# AMC_Connector.net
KiCad netlist of a schematic drawn in Altium Designer
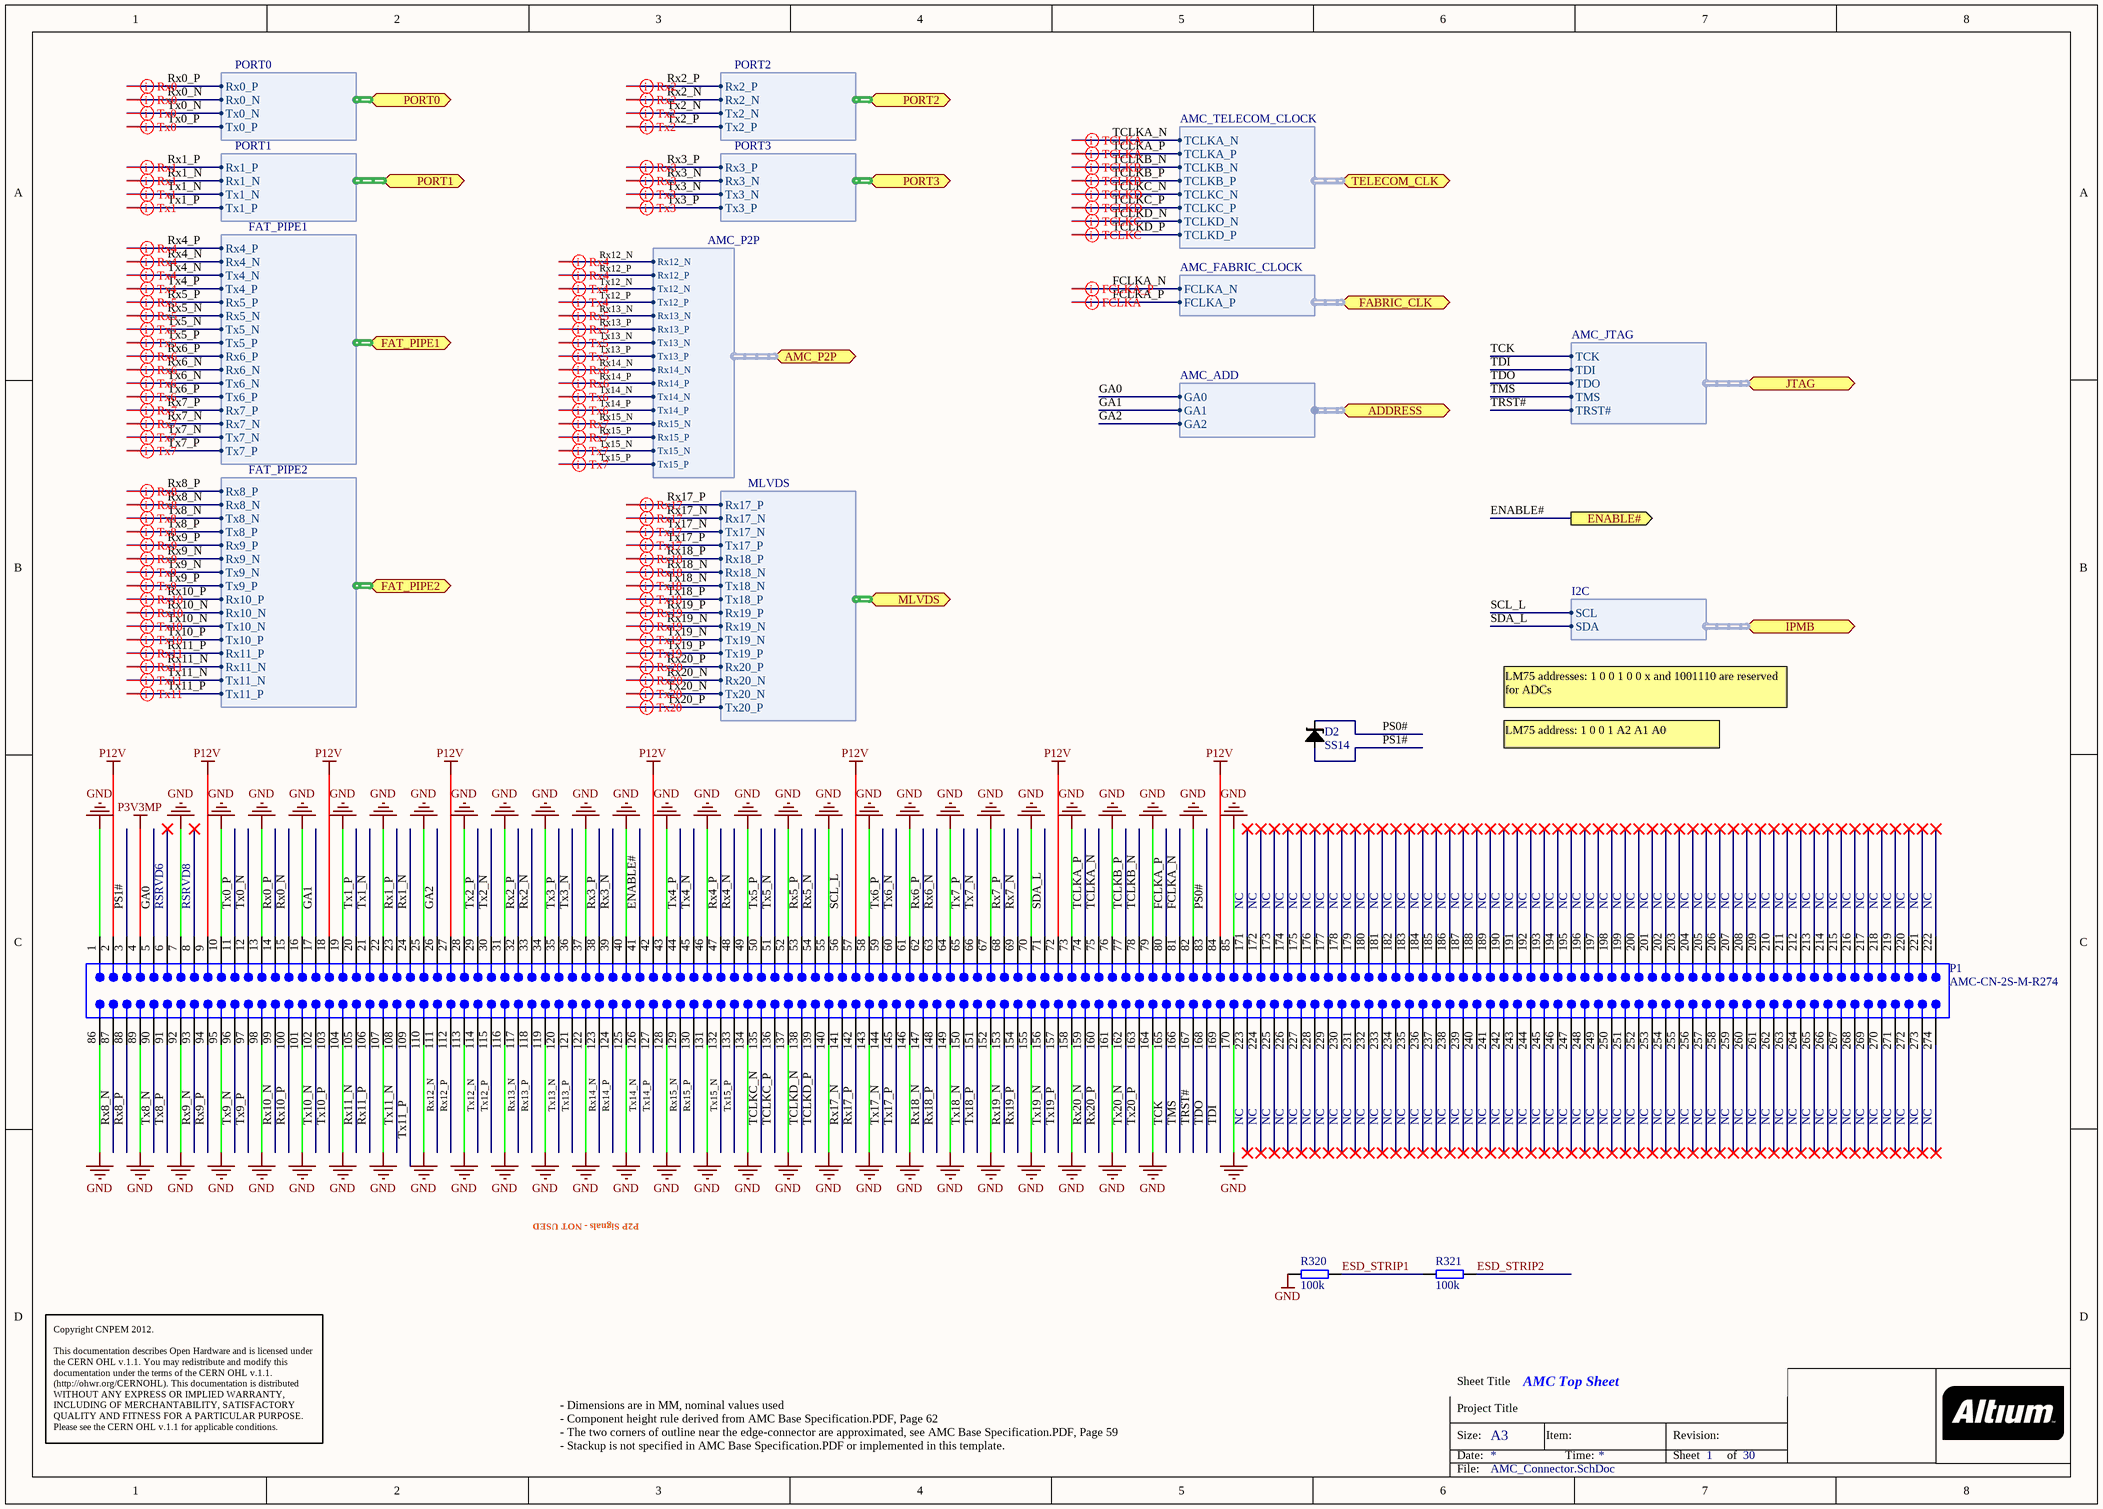
[diagram p0: AMC_Connector.SchDoc]

(export (version "E")
  (design (tool "Eeschema 10.0.6"))
  (components
    (comp (ref "D2")
      (value "SS14")
      (footprint "DO-214AC/SMA")
      (description "1A 80V shottky diode (Maritex)")
      (libsource (lib "LIBRARY_SCH") (part "D_SS14"))
    )
    (comp (ref "P1")
      (value "AMC-CN-2S-M-R274")
      (footprint "AMC-GF-2D-750-O274")
      (description "Golden finger, AMC, Dual, Opposite, Pitch 0.75mm, 170-Position")
      (fields (field (name "PUBLISHER") "Altium"))
      (libsource (lib "Altium Shanghai") (part "CMP-0001-00058-2"))
    )
    (comp (ref "R320")
      (value "100k")
      (footprint "1206R")
      (description "SMD Resistor")
      (libsource (lib "LIBRARY_SCH") (part "RES_1206"))
    )
    (comp (ref "R321")
      (value "100k")
      (footprint "1206R")
      (description "SMD Resistor")
      (libsource (lib "LIBRARY_SCH") (part "RES_1206"))
    )
  )
  (nets
    (net (code "14") (name "/ENABLE#") (class "Default")
      (node (ref "P1") (pin "41") (pinfunction "41_41") (pintype "passive"))
    )
    (net (code "15") (name "/ESD_STRIP1") (class "Default")
      (node (ref "R320") (pin "2") (pinfunction "2_2") (pintype "passive"))
      (node (ref "R321") (pin "1") (pinfunction "1_1") (pintype "passive"))
    )
    (net (code "16") (name "/ESD_STRIP2") (class "Default")
      (node (ref "R321") (pin "2") (pinfunction "2_2") (pintype "passive"))
    )
    (net (code "17") (name "/FCLKA_N") (class "Default")
      (node (ref "P1") (pin "81") (pinfunction "81_81") (pintype "passive"))
    )
    (net (code "18") (name "/FCLKA_P") (class "Default")
      (node (ref "P1") (pin "80") (pinfunction "80_80") (pintype "passive"))
    )
    (net (code "19") (name "/GA0") (class "Default")
      (node (ref "P1") (pin "5") (pinfunction "5_5") (pintype "passive"))
    )
    (net (code "20") (name "/GA1") (class "Default")
      (node (ref "P1") (pin "17") (pinfunction "17_17") (pintype "passive"))
    )
    (net (code "21") (name "/GA2") (class "Default")
      (node (ref "P1") (pin "26") (pinfunction "26_26") (pintype "passive"))
    )
    (net (code "22") (name "/PS0#") (class "Default")
      (node (ref "D2") (pin "K") (pinfunction "K_K") (pintype "passive"))
      (node (ref "P1") (pin "83") (pinfunction "83_83") (pintype "passive"))
    )
    (net (code "23") (name "/PS1#") (class "Default")
      (node (ref "D2") (pin "A") (pinfunction "A_A") (pintype "passive"))
      (node (ref "P1") (pin "3") (pinfunction "3_3") (pintype "passive"))
    )
    (net (code "24") (name "/Rx0_N") (class "Default")
      (node (ref "P1") (pin "15") (pinfunction "15_15") (pintype "passive"))
    )
    (net (code "25") (name "/Rx0_P") (class "Default")
      (node (ref "P1") (pin "14") (pinfunction "14_14") (pintype "passive"))
    )
    (net (code "26") (name "/Rx1_N") (class "Default")
      (node (ref "P1") (pin "24") (pinfunction "24_24") (pintype "passive"))
    )
    (net (code "27") (name "/Rx1_P") (class "Default")
      (node (ref "P1") (pin "23") (pinfunction "23_23") (pintype "passive"))
    )
    (net (code "28") (name "/Rx2_N") (class "Default")
      (node (ref "P1") (pin "33") (pinfunction "33_33") (pintype "passive"))
    )
    (net (code "29") (name "/Rx2_P") (class "Default")
      (node (ref "P1") (pin "32") (pinfunction "32_32") (pintype "passive"))
    )
    (net (code "30") (name "/Rx3_N") (class "Default")
      (node (ref "P1") (pin "39") (pinfunction "39_39") (pintype "passive"))
    )
    (net (code "31") (name "/Rx3_P") (class "Default")
      (node (ref "P1") (pin "38") (pinfunction "38_38") (pintype "passive"))
    )
    (net (code "32") (name "/Rx4_N") (class "Default")
      (node (ref "P1") (pin "48") (pinfunction "48_48") (pintype "passive"))
    )
    (net (code "33") (name "/Rx4_P") (class "Default")
      (node (ref "P1") (pin "47") (pinfunction "47_47") (pintype "passive"))
    )
    (net (code "34") (name "/Rx5_N") (class "Default")
      (node (ref "P1") (pin "54") (pinfunction "54_54") (pintype "passive"))
    )
    (net (code "35") (name "/Rx5_P") (class "Default")
      (node (ref "P1") (pin "53") (pinfunction "53_53") (pintype "passive"))
    )
    (net (code "36") (name "/Rx6_N") (class "Default")
      (node (ref "P1") (pin "63") (pinfunction "63_63") (pintype "passive"))
    )
    (net (code "37") (name "/Rx6_P") (class "Default")
      (node (ref "P1") (pin "62") (pinfunction "62_62") (pintype "passive"))
    )
    (net (code "38") (name "/Rx7_N") (class "Default")
      (node (ref "P1") (pin "69") (pinfunction "69_69") (pintype "passive"))
    )
    (net (code "39") (name "/Rx7_P") (class "Default")
      (node (ref "P1") (pin "68") (pinfunction "68_68") (pintype "passive"))
    )
    (net (code "40") (name "/Rx8_N") (class "Default")
      (node (ref "P1") (pin "87") (pinfunction "87_87") (pintype "passive"))
    )
    (net (code "41") (name "/Rx8_P") (class "Default")
      (node (ref "P1") (pin "88") (pinfunction "88_88") (pintype "passive"))
    )
    (net (code "42") (name "/Rx9_N") (class "Default")
      (node (ref "P1") (pin "93") (pinfunction "93_93") (pintype "passive"))
    )
    (net (code "43") (name "/Rx9_P") (class "Default")
      (node (ref "P1") (pin "94") (pinfunction "94_94") (pintype "passive"))
    )
    (net (code "44") (name "/Rx10_N") (class "Default")
      (node (ref "P1") (pin "99") (pinfunction "99_99") (pintype "passive"))
    )
    (net (code "45") (name "/Rx10_P") (class "Default")
      (node (ref "P1") (pin "100") (pinfunction "100_100") (pintype "passive"))
    )
    (net (code "46") (name "/Rx11_N") (class "Default")
      (node (ref "P1") (pin "105") (pinfunction "105_105") (pintype "passive"))
    )
    (net (code "47") (name "/Rx11_P") (class "Default")
      (node (ref "P1") (pin "106") (pinfunction "106_106") (pintype "passive"))
    )
    (net (code "48") (name "/Rx12_N") (class "Default")
      (node (ref "P1") (pin "111") (pinfunction "111_111") (pintype "passive"))
    )
    (net (code "49") (name "/Rx12_P") (class "Default")
      (node (ref "P1") (pin "112") (pinfunction "112_112") (pintype "passive"))
    )
    (net (code "50") (name "/Rx13_N") (class "Default")
      (node (ref "P1") (pin "117") (pinfunction "117_117") (pintype "passive"))
    )
    (net (code "51") (name "/Rx13_P") (class "Default")
      (node (ref "P1") (pin "118") (pinfunction "118_118") (pintype "passive"))
    )
    (net (code "52") (name "/Rx14_N") (class "Default")
      (node (ref "P1") (pin "123") (pinfunction "123_123") (pintype "passive"))
    )
    (net (code "53") (name "/Rx14_P") (class "Default")
      (node (ref "P1") (pin "124") (pinfunction "124_124") (pintype "passive"))
    )
    (net (code "54") (name "/Rx15_N") (class "Default")
      (node (ref "P1") (pin "129") (pinfunction "129_129") (pintype "passive"))
    )
    (net (code "55") (name "/Rx15_P") (class "Default")
      (node (ref "P1") (pin "130") (pinfunction "130_130") (pintype "passive"))
    )
    (net (code "56") (name "/Rx17_N") (class "Default")
      (node (ref "P1") (pin "141") (pinfunction "141_141") (pintype "passive"))
    )
    (net (code "57") (name "/Rx17_P") (class "Default")
      (node (ref "P1") (pin "142") (pinfunction "142_142") (pintype "passive"))
    )
    (net (code "58") (name "/Rx18_N") (class "Default")
      (node (ref "P1") (pin "147") (pinfunction "147_147") (pintype "passive"))
    )
    (net (code "59") (name "/Rx18_P") (class "Default")
      (node (ref "P1") (pin "148") (pinfunction "148_148") (pintype "passive"))
    )
    (net (code "60") (name "/Rx19_N") (class "Default")
      (node (ref "P1") (pin "153") (pinfunction "153_153") (pintype "passive"))
    )
    (net (code "61") (name "/Rx19_P") (class "Default")
      (node (ref "P1") (pin "154") (pinfunction "154_154") (pintype "passive"))
    )
    (net (code "62") (name "/Rx20_N") (class "Default")
      (node (ref "P1") (pin "159") (pinfunction "159_159") (pintype "passive"))
    )
    (net (code "63") (name "/Rx20_P") (class "Default")
      (node (ref "P1") (pin "160") (pinfunction "160_160") (pintype "passive"))
    )
    (net (code "64") (name "/SCL_L") (class "Default")
      (node (ref "P1") (pin "56") (pinfunction "56_56") (pintype "passive"))
    )
    (net (code "65") (name "/SDA_L") (class "Default")
      (node (ref "P1") (pin "71") (pinfunction "71_71") (pintype "passive"))
    )
    (net (code "66") (name "/TCK") (class "Default")
      (node (ref "P1") (pin "165") (pinfunction "165_165") (pintype "passive"))
    )
    (net (code "67") (name "/TCLKA_N") (class "Default")
      (node (ref "P1") (pin "75") (pinfunction "75_75") (pintype "passive"))
    )
    (net (code "68") (name "/TCLKA_P") (class "Default")
      (node (ref "P1") (pin "74") (pinfunction "74_74") (pintype "passive"))
    )
    (net (code "69") (name "/TCLKB_N") (class "Default")
      (node (ref "P1") (pin "78") (pinfunction "78_78") (pintype "passive"))
    )
    (net (code "70") (name "/TCLKB_P") (class "Default")
      (node (ref "P1") (pin "77") (pinfunction "77_77") (pintype "passive"))
    )
    (net (code "71") (name "/TCLKC_N") (class "Default")
      (node (ref "P1") (pin "135") (pinfunction "135_135") (pintype "passive"))
    )
    (net (code "72") (name "/TCLKC_P") (class "Default")
      (node (ref "P1") (pin "136") (pinfunction "136_136") (pintype "passive"))
    )
    (net (code "73") (name "/TCLKD_N") (class "Default")
      (node (ref "P1") (pin "138") (pinfunction "138_138") (pintype "passive"))
    )
    (net (code "74") (name "/TCLKD_P") (class "Default")
      (node (ref "P1") (pin "139") (pinfunction "139_139") (pintype "passive"))
    )
    (net (code "75") (name "/TDI") (class "Default")
      (node (ref "P1") (pin "169") (pinfunction "169_169") (pintype "passive"))
    )
    (net (code "76") (name "/TDO") (class "Default")
      (node (ref "P1") (pin "168") (pinfunction "168_168") (pintype "passive"))
    )
    (net (code "77") (name "/TMS") (class "Default")
      (node (ref "P1") (pin "166") (pinfunction "166_166") (pintype "passive"))
    )
    (net (code "78") (name "/TRST#") (class "Default")
      (node (ref "P1") (pin "167") (pinfunction "167_167") (pintype "passive"))
    )
    (net (code "79") (name "/Tx0_N") (class "Default")
      (node (ref "P1") (pin "12") (pinfunction "12_12") (pintype "passive"))
    )
    (net (code "80") (name "/Tx0_P") (class "Default")
      (node (ref "P1") (pin "11") (pinfunction "11_11") (pintype "passive"))
    )
    (net (code "81") (name "/Tx1_N") (class "Default")
      (node (ref "P1") (pin "21") (pinfunction "21_21") (pintype "passive"))
    )
    (net (code "82") (name "/Tx1_P") (class "Default")
      (node (ref "P1") (pin "20") (pinfunction "20_20") (pintype "passive"))
    )
    (net (code "83") (name "/Tx2_N") (class "Default")
      (node (ref "P1") (pin "30") (pinfunction "30_30") (pintype "passive"))
    )
    (net (code "84") (name "/Tx2_P") (class "Default")
      (node (ref "P1") (pin "29") (pinfunction "29_29") (pintype "passive"))
    )
    (net (code "85") (name "/Tx3_N") (class "Default")
      (node (ref "P1") (pin "36") (pinfunction "36_36") (pintype "passive"))
    )
    (net (code "86") (name "/Tx3_P") (class "Default")
      (node (ref "P1") (pin "35") (pinfunction "35_35") (pintype "passive"))
    )
    (net (code "87") (name "/Tx4_N") (class "Default")
      (node (ref "P1") (pin "45") (pinfunction "45_45") (pintype "passive"))
    )
    (net (code "88") (name "/Tx4_P") (class "Default")
      (node (ref "P1") (pin "44") (pinfunction "44_44") (pintype "passive"))
    )
    (net (code "89") (name "/Tx5_N") (class "Default")
      (node (ref "P1") (pin "51") (pinfunction "51_51") (pintype "passive"))
    )
    (net (code "90") (name "/Tx5_P") (class "Default")
      (node (ref "P1") (pin "50") (pinfunction "50_50") (pintype "passive"))
    )
    (net (code "91") (name "/Tx6_N") (class "Default")
      (node (ref "P1") (pin "60") (pinfunction "60_60") (pintype "passive"))
    )
    (net (code "92") (name "/Tx6_P") (class "Default")
      (node (ref "P1") (pin "59") (pinfunction "59_59") (pintype "passive"))
    )
    (net (code "93") (name "/Tx7_N") (class "Default")
      (node (ref "P1") (pin "66") (pinfunction "66_66") (pintype "passive"))
    )
    (net (code "94") (name "/Tx7_P") (class "Default")
      (node (ref "P1") (pin "65") (pinfunction "65_65") (pintype "passive"))
    )
    (net (code "95") (name "/Tx8_N") (class "Default")
      (node (ref "P1") (pin "90") (pinfunction "90_90") (pintype "passive"))
    )
    (net (code "96") (name "/Tx8_P") (class "Default")
      (node (ref "P1") (pin "91") (pinfunction "91_91") (pintype "passive"))
    )
    (net (code "97") (name "/Tx9_N") (class "Default")
      (node (ref "P1") (pin "96") (pinfunction "96_96") (pintype "passive"))
    )
    (net (code "98") (name "/Tx9_P") (class "Default")
      (node (ref "P1") (pin "97") (pinfunction "97_97") (pintype "passive"))
    )
    (net (code "99") (name "/Tx10_N") (class "Default")
      (node (ref "P1") (pin "102") (pinfunction "102_102") (pintype "passive"))
    )
    (net (code "100") (name "/Tx10_P") (class "Default")
      (node (ref "P1") (pin "103") (pinfunction "103_103") (pintype "passive"))
    )
    (net (code "101") (name "/Tx11_N") (class "Default")
      (node (ref "P1") (pin "108") (pinfunction "108_108") (pintype "passive"))
    )
    (net (code "102") (name "/Tx11_P") (class "Default")
      (node (ref "P1") (pin "109") (pinfunction "109_109") (pintype "passive"))
    )
    (net (code "103") (name "/Tx12_N") (class "Default")
      (node (ref "P1") (pin "114") (pinfunction "114_114") (pintype "passive"))
    )
    (net (code "104") (name "/Tx12_P") (class "Default")
      (node (ref "P1") (pin "115") (pinfunction "115_115") (pintype "passive"))
    )
    (net (code "105") (name "/Tx13_N") (class "Default")
      (node (ref "P1") (pin "120") (pinfunction "120_120") (pintype "passive"))
    )
    (net (code "106") (name "/Tx13_P") (class "Default")
      (node (ref "P1") (pin "121") (pinfunction "121_121") (pintype "passive"))
    )
    (net (code "107") (name "/Tx14_N") (class "Default")
      (node (ref "P1") (pin "126") (pinfunction "126_126") (pintype "passive"))
    )
    (net (code "108") (name "/Tx14_P") (class "Default")
      (node (ref "P1") (pin "127") (pinfunction "127_127") (pintype "passive"))
    )
    (net (code "109") (name "/Tx15_N") (class "Default")
      (node (ref "P1") (pin "132") (pinfunction "132_132") (pintype "passive"))
    )
    (net (code "110") (name "/Tx15_P") (class "Default")
      (node (ref "P1") (pin "133") (pinfunction "133_133") (pintype "passive"))
    )
    (net (code "111") (name "/Tx17_N") (class "Default")
      (node (ref "P1") (pin "144") (pinfunction "144_144") (pintype "passive"))
    )
    (net (code "112") (name "/Tx17_P") (class "Default")
      (node (ref "P1") (pin "145") (pinfunction "145_145") (pintype "passive"))
    )
    (net (code "113") (name "/Tx18_N") (class "Default")
      (node (ref "P1") (pin "150") (pinfunction "150_150") (pintype "passive"))
    )
    (net (code "114") (name "/Tx18_P") (class "Default")
      (node (ref "P1") (pin "151") (pinfunction "151_151") (pintype "passive"))
    )
    (net (code "115") (name "/Tx19_N") (class "Default")
      (node (ref "P1") (pin "156") (pinfunction "156_156") (pintype "passive"))
    )
    (net (code "116") (name "/Tx19_P") (class "Default")
      (node (ref "P1") (pin "157") (pinfunction "157_157") (pintype "passive"))
    )
    (net (code "117") (name "/Tx20_N") (class "Default")
      (node (ref "P1") (pin "162") (pinfunction "162_162") (pintype "passive"))
    )
    (net (code "118") (name "/Tx20_P") (class "Default")
      (node (ref "P1") (pin "163") (pinfunction "163_163") (pintype "passive"))
    )
    (net (code "132") (name "GND") (class "Default")
      (node (ref "P1") (pin "1") (pinfunction "1_1") (pintype "passive"))
      (node (ref "P1") (pin "10") (pinfunction "10_10") (pintype "passive"))
      (node (ref "P1") (pin "101") (pinfunction "101_101") (pintype "passive"))
      (node (ref "P1") (pin "104") (pinfunction "104_104") (pintype "passive"))
      (node (ref "P1") (pin "107") (pinfunction "107_107") (pintype "passive"))
      (node (ref "P1") (pin "110") (pinfunction "110_110") (pintype "passive"))
      (node (ref "P1") (pin "113") (pinfunction "113_113") (pintype "passive"))
      (node (ref "P1") (pin "116") (pinfunction "116_116") (pintype "passive"))
      (node (ref "P1") (pin "119") (pinfunction "119_119") (pintype "passive"))
      (node (ref "P1") (pin "122") (pinfunction "122_122") (pintype "passive"))
      (node (ref "P1") (pin "125") (pinfunction "125_125") (pintype "passive"))
      (node (ref "P1") (pin "128") (pinfunction "128_128") (pintype "passive"))
      (node (ref "P1") (pin "13") (pinfunction "13_13") (pintype "passive"))
      (node (ref "P1") (pin "131") (pinfunction "131_131") (pintype "passive"))
      (node (ref "P1") (pin "134") (pinfunction "134_134") (pintype "passive"))
      (node (ref "P1") (pin "137") (pinfunction "137_137") (pintype "passive"))
      (node (ref "P1") (pin "140") (pinfunction "140_140") (pintype "passive"))
      (node (ref "P1") (pin "143") (pinfunction "143_143") (pintype "passive"))
      (node (ref "P1") (pin "146") (pinfunction "146_146") (pintype "passive"))
      (node (ref "P1") (pin "149") (pinfunction "149_149") (pintype "passive"))
      (node (ref "P1") (pin "152") (pinfunction "152_152") (pintype "passive"))
      (node (ref "P1") (pin "155") (pinfunction "155_155") (pintype "passive"))
      (node (ref "P1") (pin "158") (pinfunction "158_158") (pintype "passive"))
      (node (ref "P1") (pin "16") (pinfunction "16_16") (pintype "passive"))
      (node (ref "P1") (pin "161") (pinfunction "161_161") (pintype "passive"))
      (node (ref "P1") (pin "164") (pinfunction "164_164") (pintype "passive"))
      (node (ref "P1") (pin "170") (pinfunction "170_170") (pintype "passive"))
      (node (ref "P1") (pin "19") (pinfunction "19_19") (pintype "passive"))
      (node (ref "P1") (pin "22") (pinfunction "22_22") (pintype "passive"))
      (node (ref "P1") (pin "25") (pinfunction "25_25") (pintype "passive"))
      (node (ref "P1") (pin "28") (pinfunction "28_28") (pintype "passive"))
      (node (ref "P1") (pin "31") (pinfunction "31_31") (pintype "passive"))
      (node (ref "P1") (pin "34") (pinfunction "34_34") (pintype "passive"))
      (node (ref "P1") (pin "37") (pinfunction "37_37") (pintype "passive"))
      (node (ref "P1") (pin "40") (pinfunction "40_40") (pintype "passive"))
      (node (ref "P1") (pin "43") (pinfunction "43_43") (pintype "passive"))
      (node (ref "P1") (pin "46") (pinfunction "46_46") (pintype "passive"))
      (node (ref "P1") (pin "49") (pinfunction "49_49") (pintype "passive"))
      (node (ref "P1") (pin "52") (pinfunction "52_52") (pintype "passive"))
      (node (ref "P1") (pin "55") (pinfunction "55_55") (pintype "passive"))
      (node (ref "P1") (pin "58") (pinfunction "58_58") (pintype "passive"))
      (node (ref "P1") (pin "61") (pinfunction "61_61") (pintype "passive"))
      (node (ref "P1") (pin "64") (pinfunction "64_64") (pintype "passive"))
      (node (ref "P1") (pin "67") (pinfunction "67_67") (pintype "passive"))
      (node (ref "P1") (pin "7") (pinfunction "7_7") (pintype "passive"))
      (node (ref "P1") (pin "70") (pinfunction "70_70") (pintype "passive"))
      (node (ref "P1") (pin "73") (pinfunction "73_73") (pintype "passive"))
      (node (ref "P1") (pin "76") (pinfunction "76_76") (pintype "passive"))
      (node (ref "P1") (pin "79") (pinfunction "79_79") (pintype "passive"))
      (node (ref "P1") (pin "82") (pinfunction "82_82") (pintype "passive"))
      (node (ref "P1") (pin "85") (pinfunction "85_85") (pintype "passive"))
      (node (ref "P1") (pin "86") (pinfunction "86_86") (pintype "passive"))
      (node (ref "P1") (pin "89") (pinfunction "89_89") (pintype "passive"))
      (node (ref "P1") (pin "92") (pinfunction "92_92") (pintype "passive"))
      (node (ref "P1") (pin "95") (pinfunction "95_95") (pintype "passive"))
      (node (ref "P1") (pin "98") (pinfunction "98_98") (pintype "passive"))
      (node (ref "R320") (pin "1") (pinfunction "1_1") (pintype "passive"))
    )
    (net (code "133") (name "P3V3MP") (class "Default")
      (node (ref "P1") (pin "4") (pinfunction "4_4") (pintype "passive"))
    )
    (net (code "134") (name "P12V") (class "Default")
      (node (ref "P1") (pin "18") (pinfunction "18_18") (pintype "passive"))
      (node (ref "P1") (pin "2") (pinfunction "2_2") (pintype "passive"))
      (node (ref "P1") (pin "27") (pinfunction "27_27") (pintype "passive"))
      (node (ref "P1") (pin "42") (pinfunction "42_42") (pintype "passive"))
      (node (ref "P1") (pin "57") (pinfunction "57_57") (pintype "passive"))
      (node (ref "P1") (pin "72") (pinfunction "72_72") (pintype "passive"))
      (node (ref "P1") (pin "84") (pinfunction "84_84") (pintype "passive"))
      (node (ref "P1") (pin "9") (pinfunction "9_9") (pintype "passive"))
    )
    (net (code "135") (name "unconnected-(P1-Pad6)") (class "Default")
      (node (ref "P1") (pin "6") (pinfunction "6_6") (pintype "passive+no_connect"))
    )
    (net (code "136") (name "unconnected-(P1-Pad8)") (class "Default")
      (node (ref "P1") (pin "8") (pinfunction "8_8") (pintype "passive+no_connect"))
    )
    (net (code "137") (name "unconnected-(P1-Pad171)") (class "Default")
      (node (ref "P1") (pin "171") (pinfunction "171_171") (pintype "passive+no_connect"))
    )
    (net (code "138") (name "unconnected-(P1-Pad172)") (class "Default")
      (node (ref "P1") (pin "172") (pinfunction "172_172") (pintype "passive+no_connect"))
    )
    (net (code "139") (name "unconnected-(P1-Pad173)") (class "Default")
      (node (ref "P1") (pin "173") (pinfunction "173_173") (pintype "passive+no_connect"))
    )
    (net (code "140") (name "unconnected-(P1-Pad174)") (class "Default")
      (node (ref "P1") (pin "174") (pinfunction "174_174") (pintype "passive+no_connect"))
    )
    (net (code "141") (name "unconnected-(P1-Pad175)") (class "Default")
      (node (ref "P1") (pin "175") (pinfunction "175_175") (pintype "passive+no_connect"))
    )
    (net (code "142") (name "unconnected-(P1-Pad176)") (class "Default")
      (node (ref "P1") (pin "176") (pinfunction "176_176") (pintype "passive+no_connect"))
    )
    (net (code "143") (name "unconnected-(P1-Pad177)") (class "Default")
      (node (ref "P1") (pin "177") (pinfunction "177_177") (pintype "passive+no_connect"))
    )
    (net (code "144") (name "unconnected-(P1-Pad178)") (class "Default")
      (node (ref "P1") (pin "178") (pinfunction "178_178") (pintype "passive+no_connect"))
    )
    (net (code "145") (name "unconnected-(P1-Pad179)") (class "Default")
      (node (ref "P1") (pin "179") (pinfunction "179_179") (pintype "passive+no_connect"))
    )
    (net (code "146") (name "unconnected-(P1-Pad180)") (class "Default")
      (node (ref "P1") (pin "180") (pinfunction "180_180") (pintype "passive+no_connect"))
    )
    (net (code "147") (name "unconnected-(P1-Pad181)") (class "Default")
      (node (ref "P1") (pin "181") (pinfunction "181_181") (pintype "passive+no_connect"))
    )
    (net (code "148") (name "unconnected-(P1-Pad182)") (class "Default")
      (node (ref "P1") (pin "182") (pinfunction "182_182") (pintype "passive+no_connect"))
    )
    (net (code "149") (name "unconnected-(P1-Pad183)") (class "Default")
      (node (ref "P1") (pin "183") (pinfunction "183_183") (pintype "passive+no_connect"))
    )
    (net (code "150") (name "unconnected-(P1-Pad184)") (class "Default")
      (node (ref "P1") (pin "184") (pinfunction "184_184") (pintype "passive+no_connect"))
    )
    (net (code "151") (name "unconnected-(P1-Pad185)") (class "Default")
      (node (ref "P1") (pin "185") (pinfunction "185_185") (pintype "passive+no_connect"))
    )
    (net (code "152") (name "unconnected-(P1-Pad186)") (class "Default")
      (node (ref "P1") (pin "186") (pinfunction "186_186") (pintype "passive+no_connect"))
    )
    (net (code "153") (name "unconnected-(P1-Pad187)") (class "Default")
      (node (ref "P1") (pin "187") (pinfunction "187_187") (pintype "passive+no_connect"))
    )
    (net (code "154") (name "unconnected-(P1-Pad188)") (class "Default")
      (node (ref "P1") (pin "188") (pinfunction "188_188") (pintype "passive+no_connect"))
    )
    (net (code "155") (name "unconnected-(P1-Pad189)") (class "Default")
      (node (ref "P1") (pin "189") (pinfunction "189_189") (pintype "passive+no_connect"))
    )
    (net (code "156") (name "unconnected-(P1-Pad190)") (class "Default")
      (node (ref "P1") (pin "190") (pinfunction "190_190") (pintype "passive+no_connect"))
    )
    (net (code "157") (name "unconnected-(P1-Pad191)") (class "Default")
      (node (ref "P1") (pin "191") (pinfunction "191_191") (pintype "passive+no_connect"))
    )
    (net (code "158") (name "unconnected-(P1-Pad192)") (class "Default")
      (node (ref "P1") (pin "192") (pinfunction "192_192") (pintype "passive+no_connect"))
    )
    (net (code "159") (name "unconnected-(P1-Pad193)") (class "Default")
      (node (ref "P1") (pin "193") (pinfunction "193_193") (pintype "passive+no_connect"))
    )
    (net (code "160") (name "unconnected-(P1-Pad194)") (class "Default")
      (node (ref "P1") (pin "194") (pinfunction "194_194") (pintype "passive+no_connect"))
    )
    (net (code "161") (name "unconnected-(P1-Pad195)") (class "Default")
      (node (ref "P1") (pin "195") (pinfunction "195_195") (pintype "passive+no_connect"))
    )
    (net (code "162") (name "unconnected-(P1-Pad196)") (class "Default")
      (node (ref "P1") (pin "196") (pinfunction "196_196") (pintype "passive+no_connect"))
    )
    (net (code "163") (name "unconnected-(P1-Pad197)") (class "Default")
      (node (ref "P1") (pin "197") (pinfunction "197_197") (pintype "passive+no_connect"))
    )
    (net (code "164") (name "unconnected-(P1-Pad198)") (class "Default")
      (node (ref "P1") (pin "198") (pinfunction "198_198") (pintype "passive+no_connect"))
    )
    (net (code "165") (name "unconnected-(P1-Pad199)") (class "Default")
      (node (ref "P1") (pin "199") (pinfunction "199_199") (pintype "passive+no_connect"))
    )
    (net (code "166") (name "unconnected-(P1-Pad200)") (class "Default")
      (node (ref "P1") (pin "200") (pinfunction "200_200") (pintype "passive+no_connect"))
    )
    (net (code "167") (name "unconnected-(P1-Pad201)") (class "Default")
      (node (ref "P1") (pin "201") (pinfunction "201_201") (pintype "passive+no_connect"))
    )
    (net (code "168") (name "unconnected-(P1-Pad202)") (class "Default")
      (node (ref "P1") (pin "202") (pinfunction "202_202") (pintype "passive+no_connect"))
    )
    (net (code "169") (name "unconnected-(P1-Pad203)") (class "Default")
      (node (ref "P1") (pin "203") (pinfunction "203_203") (pintype "passive+no_connect"))
    )
    (net (code "170") (name "unconnected-(P1-Pad204)") (class "Default")
      (node (ref "P1") (pin "204") (pinfunction "204_204") (pintype "passive+no_connect"))
    )
    (net (code "171") (name "unconnected-(P1-Pad205)") (class "Default")
      (node (ref "P1") (pin "205") (pinfunction "205_205") (pintype "passive+no_connect"))
    )
    (net (code "172") (name "unconnected-(P1-Pad206)") (class "Default")
      (node (ref "P1") (pin "206") (pinfunction "206_206") (pintype "passive+no_connect"))
    )
    (net (code "173") (name "unconnected-(P1-Pad207)") (class "Default")
      (node (ref "P1") (pin "207") (pinfunction "207_207") (pintype "passive+no_connect"))
    )
    (net (code "174") (name "unconnected-(P1-Pad208)") (class "Default")
      (node (ref "P1") (pin "208") (pinfunction "208_208") (pintype "passive+no_connect"))
    )
    (net (code "175") (name "unconnected-(P1-Pad209)") (class "Default")
      (node (ref "P1") (pin "209") (pinfunction "209_209") (pintype "passive+no_connect"))
    )
    (net (code "176") (name "unconnected-(P1-Pad210)") (class "Default")
      (node (ref "P1") (pin "210") (pinfunction "210_210") (pintype "passive+no_connect"))
    )
    (net (code "177") (name "unconnected-(P1-Pad211)") (class "Default")
      (node (ref "P1") (pin "211") (pinfunction "211_211") (pintype "passive+no_connect"))
    )
    (net (code "178") (name "unconnected-(P1-Pad212)") (class "Default")
      (node (ref "P1") (pin "212") (pinfunction "212_212") (pintype "passive+no_connect"))
    )
    (net (code "179") (name "unconnected-(P1-Pad213)") (class "Default")
      (node (ref "P1") (pin "213") (pinfunction "213_213") (pintype "passive+no_connect"))
    )
    (net (code "180") (name "unconnected-(P1-Pad214)") (class "Default")
      (node (ref "P1") (pin "214") (pinfunction "214_214") (pintype "passive+no_connect"))
    )
    (net (code "181") (name "unconnected-(P1-Pad215)") (class "Default")
      (node (ref "P1") (pin "215") (pinfunction "215_215") (pintype "passive+no_connect"))
    )
    (net (code "182") (name "unconnected-(P1-Pad216)") (class "Default")
      (node (ref "P1") (pin "216") (pinfunction "216_216") (pintype "passive+no_connect"))
    )
    (net (code "183") (name "unconnected-(P1-Pad217)") (class "Default")
      (node (ref "P1") (pin "217") (pinfunction "217_217") (pintype "passive+no_connect"))
    )
    (net (code "184") (name "unconnected-(P1-Pad218)") (class "Default")
      (node (ref "P1") (pin "218") (pinfunction "218_218") (pintype "passive+no_connect"))
    )
    (net (code "185") (name "unconnected-(P1-Pad219)") (class "Default")
      (node (ref "P1") (pin "219") (pinfunction "219_219") (pintype "passive+no_connect"))
    )
    (net (code "186") (name "unconnected-(P1-Pad220)") (class "Default")
      (node (ref "P1") (pin "220") (pinfunction "220_220") (pintype "passive+no_connect"))
    )
    (net (code "187") (name "unconnected-(P1-Pad221)") (class "Default")
      (node (ref "P1") (pin "221") (pinfunction "221_221") (pintype "passive+no_connect"))
    )
    (net (code "188") (name "unconnected-(P1-Pad222)") (class "Default")
      (node (ref "P1") (pin "222") (pinfunction "222_222") (pintype "passive+no_connect"))
    )
    (net (code "189") (name "unconnected-(P1-Pad223)") (class "Default")
      (node (ref "P1") (pin "223") (pinfunction "223_223") (pintype "passive+no_connect"))
    )
    (net (code "190") (name "unconnected-(P1-Pad224)") (class "Default")
      (node (ref "P1") (pin "224") (pinfunction "224_224") (pintype "passive+no_connect"))
    )
    (net (code "191") (name "unconnected-(P1-Pad225)") (class "Default")
      (node (ref "P1") (pin "225") (pinfunction "225_225") (pintype "passive+no_connect"))
    )
    (net (code "192") (name "unconnected-(P1-Pad226)") (class "Default")
      (node (ref "P1") (pin "226") (pinfunction "226_226") (pintype "passive+no_connect"))
    )
    (net (code "193") (name "unconnected-(P1-Pad227)") (class "Default")
      (node (ref "P1") (pin "227") (pinfunction "227_227") (pintype "passive+no_connect"))
    )
    (net (code "194") (name "unconnected-(P1-Pad228)") (class "Default")
      (node (ref "P1") (pin "228") (pinfunction "228_228") (pintype "passive+no_connect"))
    )
    (net (code "195") (name "unconnected-(P1-Pad229)") (class "Default")
      (node (ref "P1") (pin "229") (pinfunction "229_229") (pintype "passive+no_connect"))
    )
    (net (code "196") (name "unconnected-(P1-Pad230)") (class "Default")
      (node (ref "P1") (pin "230") (pinfunction "230_230") (pintype "passive+no_connect"))
    )
    (net (code "197") (name "unconnected-(P1-Pad231)") (class "Default")
      (node (ref "P1") (pin "231") (pinfunction "231_231") (pintype "passive+no_connect"))
    )
    (net (code "198") (name "unconnected-(P1-Pad232)") (class "Default")
      (node (ref "P1") (pin "232") (pinfunction "232_232") (pintype "passive+no_connect"))
    )
    (net (code "199") (name "unconnected-(P1-Pad233)") (class "Default")
      (node (ref "P1") (pin "233") (pinfunction "233_233") (pintype "passive+no_connect"))
    )
    (net (code "200") (name "unconnected-(P1-Pad234)") (class "Default")
      (node (ref "P1") (pin "234") (pinfunction "234_234") (pintype "passive+no_connect"))
    )
    (net (code "201") (name "unconnected-(P1-Pad235)") (class "Default")
      (node (ref "P1") (pin "235") (pinfunction "235_235") (pintype "passive+no_connect"))
    )
    (net (code "202") (name "unconnected-(P1-Pad236)") (class "Default")
      (node (ref "P1") (pin "236") (pinfunction "236_236") (pintype "passive+no_connect"))
    )
    (net (code "203") (name "unconnected-(P1-Pad237)") (class "Default")
      (node (ref "P1") (pin "237") (pinfunction "237_237") (pintype "passive+no_connect"))
    )
    (net (code "204") (name "unconnected-(P1-Pad238)") (class "Default")
      (node (ref "P1") (pin "238") (pinfunction "238_238") (pintype "passive+no_connect"))
    )
    (net (code "205") (name "unconnected-(P1-Pad239)") (class "Default")
      (node (ref "P1") (pin "239") (pinfunction "239_239") (pintype "passive+no_connect"))
    )
    (net (code "206") (name "unconnected-(P1-Pad240)") (class "Default")
      (node (ref "P1") (pin "240") (pinfunction "240_240") (pintype "passive+no_connect"))
    )
    (net (code "207") (name "unconnected-(P1-Pad241)") (class "Default")
      (node (ref "P1") (pin "241") (pinfunction "241_241") (pintype "passive+no_connect"))
    )
    (net (code "208") (name "unconnected-(P1-Pad242)") (class "Default")
      (node (ref "P1") (pin "242") (pinfunction "242_242") (pintype "passive+no_connect"))
    )
    (net (code "209") (name "unconnected-(P1-Pad243)") (class "Default")
      (node (ref "P1") (pin "243") (pinfunction "243_243") (pintype "passive+no_connect"))
    )
    (net (code "210") (name "unconnected-(P1-Pad244)") (class "Default")
      (node (ref "P1") (pin "244") (pinfunction "244_244") (pintype "passive+no_connect"))
    )
    (net (code "211") (name "unconnected-(P1-Pad245)") (class "Default")
      (node (ref "P1") (pin "245") (pinfunction "245_245") (pintype "passive+no_connect"))
    )
    (net (code "212") (name "unconnected-(P1-Pad246)") (class "Default")
      (node (ref "P1") (pin "246") (pinfunction "246_246") (pintype "passive+no_connect"))
    )
    (net (code "213") (name "unconnected-(P1-Pad247)") (class "Default")
      (node (ref "P1") (pin "247") (pinfunction "247_247") (pintype "passive+no_connect"))
    )
    (net (code "214") (name "unconnected-(P1-Pad248)") (class "Default")
      (node (ref "P1") (pin "248") (pinfunction "248_248") (pintype "passive+no_connect"))
    )
    (net (code "215") (name "unconnected-(P1-Pad249)") (class "Default")
      (node (ref "P1") (pin "249") (pinfunction "249_249") (pintype "passive+no_connect"))
    )
    (net (code "216") (name "unconnected-(P1-Pad250)") (class "Default")
      (node (ref "P1") (pin "250") (pinfunction "250_250") (pintype "passive+no_connect"))
    )
    (net (code "217") (name "unconnected-(P1-Pad251)") (class "Default")
      (node (ref "P1") (pin "251") (pinfunction "251_251") (pintype "passive+no_connect"))
    )
    (net (code "218") (name "unconnected-(P1-Pad252)") (class "Default")
      (node (ref "P1") (pin "252") (pinfunction "252_252") (pintype "passive+no_connect"))
    )
    (net (code "219") (name "unconnected-(P1-Pad253)") (class "Default")
      (node (ref "P1") (pin "253") (pinfunction "253_253") (pintype "passive+no_connect"))
    )
    (net (code "220") (name "unconnected-(P1-Pad254)") (class "Default")
      (node (ref "P1") (pin "254") (pinfunction "254_254") (pintype "passive+no_connect"))
    )
    (net (code "221") (name "unconnected-(P1-Pad255)") (class "Default")
      (node (ref "P1") (pin "255") (pinfunction "255_255") (pintype "passive+no_connect"))
    )
    (net (code "222") (name "unconnected-(P1-Pad256)") (class "Default")
      (node (ref "P1") (pin "256") (pinfunction "256_256") (pintype "passive+no_connect"))
    )
    (net (code "223") (name "unconnected-(P1-Pad257)") (class "Default")
      (node (ref "P1") (pin "257") (pinfunction "257_257") (pintype "passive+no_connect"))
    )
    (net (code "224") (name "unconnected-(P1-Pad258)") (class "Default")
      (node (ref "P1") (pin "258") (pinfunction "258_258") (pintype "passive+no_connect"))
    )
    (net (code "225") (name "unconnected-(P1-Pad259)") (class "Default")
      (node (ref "P1") (pin "259") (pinfunction "259_259") (pintype "passive+no_connect"))
    )
    (net (code "226") (name "unconnected-(P1-Pad260)") (class "Default")
      (node (ref "P1") (pin "260") (pinfunction "260_260") (pintype "passive+no_connect"))
    )
    (net (code "227") (name "unconnected-(P1-Pad261)") (class "Default")
      (node (ref "P1") (pin "261") (pinfunction "261_261") (pintype "passive+no_connect"))
    )
    (net (code "228") (name "unconnected-(P1-Pad262)") (class "Default")
      (node (ref "P1") (pin "262") (pinfunction "262_262") (pintype "passive+no_connect"))
    )
    (net (code "229") (name "unconnected-(P1-Pad263)") (class "Default")
      (node (ref "P1") (pin "263") (pinfunction "263_263") (pintype "passive+no_connect"))
    )
    (net (code "230") (name "unconnected-(P1-Pad264)") (class "Default")
      (node (ref "P1") (pin "264") (pinfunction "264_264") (pintype "passive+no_connect"))
    )
    (net (code "231") (name "unconnected-(P1-Pad265)") (class "Default")
      (node (ref "P1") (pin "265") (pinfunction "265_265") (pintype "passive+no_connect"))
    )
    (net (code "232") (name "unconnected-(P1-Pad266)") (class "Default")
      (node (ref "P1") (pin "266") (pinfunction "266_266") (pintype "passive+no_connect"))
    )
    (net (code "233") (name "unconnected-(P1-Pad267)") (class "Default")
      (node (ref "P1") (pin "267") (pinfunction "267_267") (pintype "passive+no_connect"))
    )
    (net (code "234") (name "unconnected-(P1-Pad268)") (class "Default")
      (node (ref "P1") (pin "268") (pinfunction "268_268") (pintype "passive+no_connect"))
    )
    (net (code "235") (name "unconnected-(P1-Pad269)") (class "Default")
      (node (ref "P1") (pin "269") (pinfunction "269_269") (pintype "passive+no_connect"))
    )
    (net (code "236") (name "unconnected-(P1-Pad270)") (class "Default")
      (node (ref "P1") (pin "270") (pinfunction "270_270") (pintype "passive+no_connect"))
    )
    (net (code "237") (name "unconnected-(P1-Pad271)") (class "Default")
      (node (ref "P1") (pin "271") (pinfunction "271_271") (pintype "passive+no_connect"))
    )
    (net (code "238") (name "unconnected-(P1-Pad272)") (class "Default")
      (node (ref "P1") (pin "272") (pinfunction "272_272") (pintype "passive+no_connect"))
    )
    (net (code "239") (name "unconnected-(P1-Pad273)") (class "Default")
      (node (ref "P1") (pin "273") (pinfunction "273_273") (pintype "passive+no_connect"))
    )
    (net (code "240") (name "unconnected-(P1-Pad274)") (class "Default")
      (node (ref "P1") (pin "274") (pinfunction "274_274") (pintype "passive+no_connect"))
    )
  )
)
